# power.net
KiCad netlist of a schematic drawn in Altium Designer
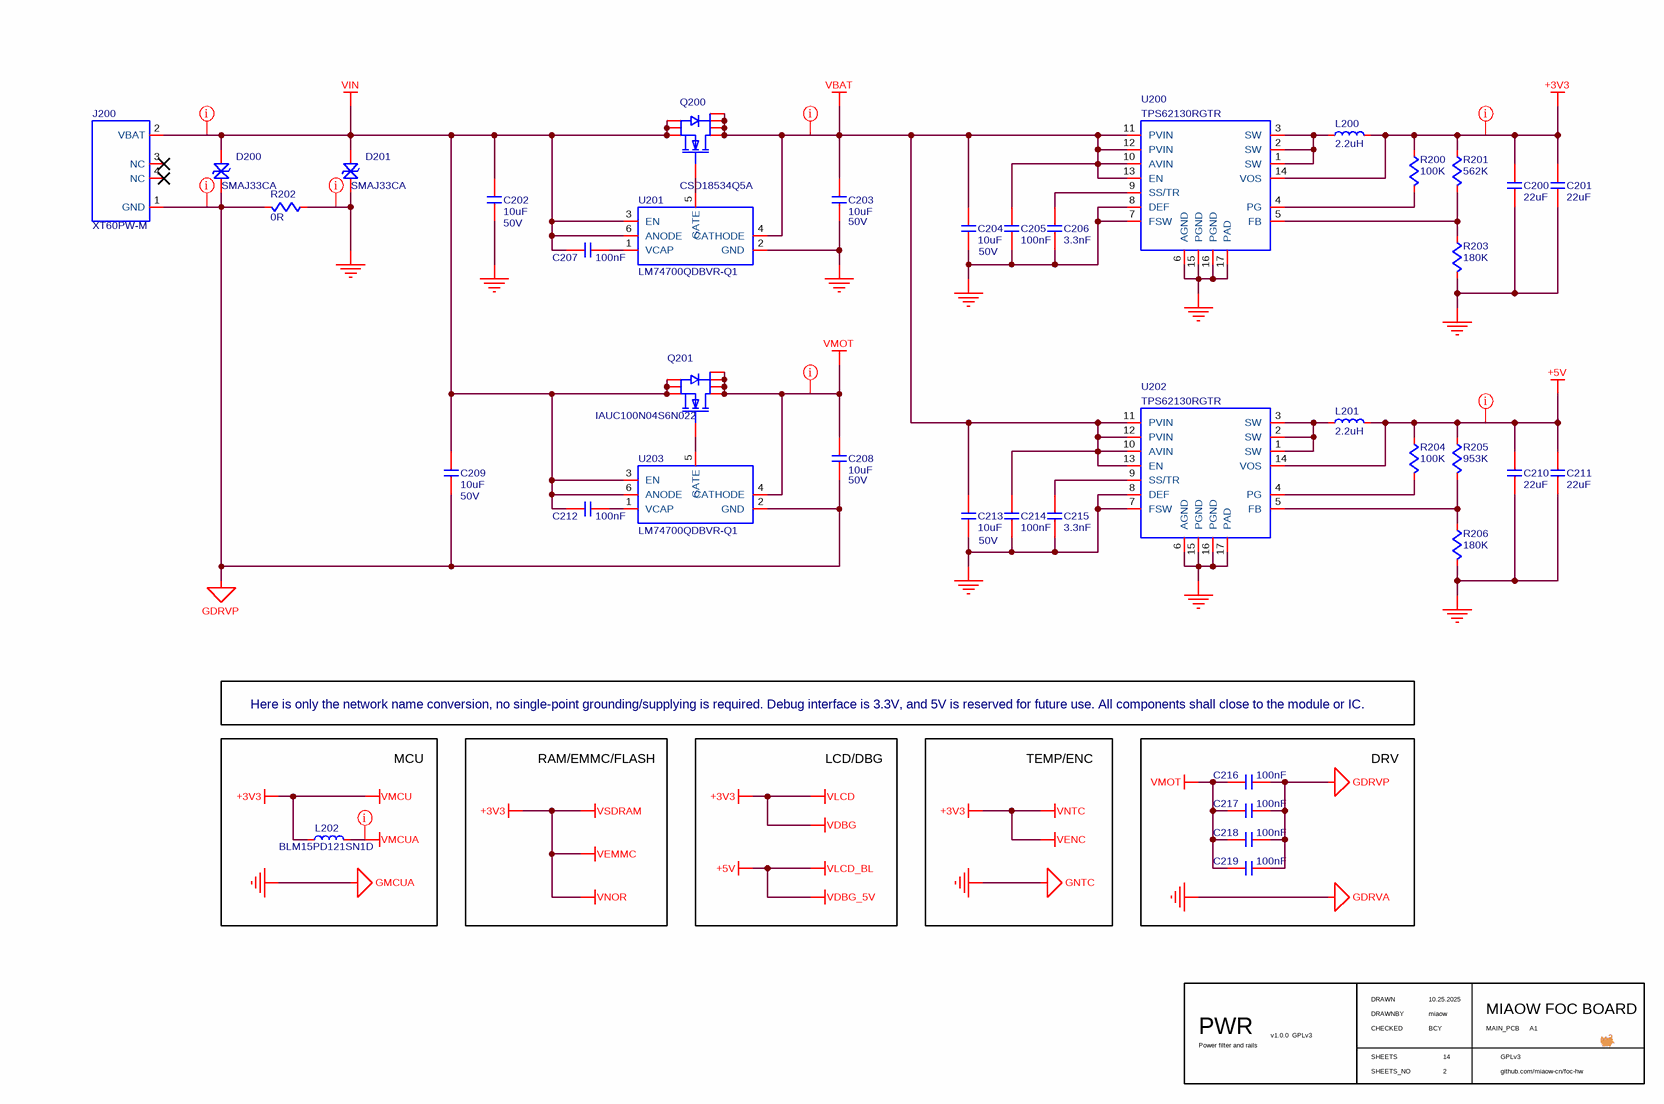
[diagram p0: power.schdoc]

(export (version "E")
  (design (tool "Eeschema 10.0.6"))
  (components
    (comp (ref "C200")
      (value "22uF")
      (footprint "mw:C0805")
      (fields (field (name "VOLTAGE") "25V") (field (name "Comment") "C-NOMO"))
      (libsource (lib "mw") (part "C-NOMO"))
    )
    (comp (ref "C201")
      (value "22uF")
      (footprint "mw:C0805")
      (fields (field (name "VOLTAGE") "25V") (field (name "Comment") "C-NOMO"))
      (libsource (lib "mw") (part "C-NOMO"))
    )
    (comp (ref "C202")
      (value "10uF")
      (footprint "mw:C0805")
      (fields (field (name "VOLTAGE") "50V") (field (name "Comment") "C-NOMO"))
      (libsource (lib "mw") (part "C-NOMO"))
    )
    (comp (ref "C203")
      (value "10uF")
      (footprint "mw:C0805")
      (fields (field (name "VOLTAGE") "50V") (field (name "Comment") "C-NOMO"))
      (libsource (lib "mw") (part "C-NOMO"))
    )
    (comp (ref "C204")
      (value "10uF")
      (footprint "mw:C0805")
      (fields (field (name "VOLTAGE") "50V") (field (name "Comment") "C-NOMO"))
      (libsource (lib "mw") (part "C-NOMO"))
    )
    (comp (ref "C205")
      (value "100nF")
      (footprint "mw:C0603")
      (fields (field (name "VOLTAGE") "25V") (field (name "Comment") "C-NOMO"))
      (libsource (lib "mw") (part "C-NOMO"))
    )
    (comp (ref "C206")
      (value "3.3nF")
      (footprint "mw:C0402")
      (fields (field (name "VOLTAGE") "25V") (field (name "Comment") "C-NOMO"))
      (libsource (lib "mw") (part "C-NOMO"))
    )
    (comp (ref "C207")
      (value "100nF")
      (footprint "mw:C0402")
      (fields (field (name "VOLTAGE") "25V") (field (name "Comment") "C-NOMO"))
      (libsource (lib "mw") (part "C-NOMO"))
    )
    (comp (ref "C208")
      (value "10uF")
      (footprint "mw:C0805")
      (fields (field (name "VOLTAGE") "50V") (field (name "Comment") "C-NOMO"))
      (libsource (lib "mw") (part "C-NOMO"))
    )
    (comp (ref "C209")
      (value "10uF")
      (footprint "mw:C0805")
      (fields (field (name "VOLTAGE") "50V") (field (name "Comment") "C-NOMO"))
      (libsource (lib "mw") (part "C-NOMO"))
    )
    (comp (ref "C210")
      (value "22uF")
      (footprint "mw:C0805")
      (fields (field (name "VOLTAGE") "25V") (field (name "Comment") "C-NOMO"))
      (libsource (lib "mw") (part "C-NOMO"))
    )
    (comp (ref "C211")
      (value "22uF")
      (footprint "mw:C0805")
      (fields (field (name "VOLTAGE") "25V") (field (name "Comment") "C-NOMO"))
      (libsource (lib "mw") (part "C-NOMO"))
    )
    (comp (ref "C212")
      (value "100nF")
      (footprint "mw:C0402")
      (fields (field (name "VOLTAGE") "25V") (field (name "Comment") "C-NOMO"))
      (libsource (lib "mw") (part "C-NOMO"))
    )
    (comp (ref "C213")
      (value "10uF")
      (footprint "mw:C0805")
      (fields (field (name "VOLTAGE") "50V") (field (name "Comment") "C-NOMO"))
      (libsource (lib "mw") (part "C-NOMO"))
    )
    (comp (ref "C214")
      (value "100nF")
      (footprint "mw:C0603")
      (fields (field (name "VOLTAGE") "25V") (field (name "Comment") "C-NOMO"))
      (libsource (lib "mw") (part "C-NOMO"))
    )
    (comp (ref "C215")
      (value "3.3nF")
      (footprint "mw:C0402")
      (fields (field (name "VOLTAGE") "25V") (field (name "Comment") "C-NOMO"))
      (libsource (lib "mw") (part "C-NOMO"))
    )
    (comp (ref "C216")
      (value "100nF")
      (footprint "mw:C0603")
      (fields (field (name "VOLTAGE") "25V") (field (name "Comment") "C-NOMO"))
      (libsource (lib "mw") (part "C-NOMO"))
    )
    (comp (ref "C217")
      (value "100nF")
      (footprint "mw:C0603")
      (fields (field (name "VOLTAGE") "25V") (field (name "Comment") "C-NOMO"))
      (libsource (lib "mw") (part "C-NOMO"))
    )
    (comp (ref "C218")
      (value "100nF")
      (footprint "mw:C0603")
      (fields (field (name "VOLTAGE") "25V") (field (name "Comment") "C-NOMO"))
      (libsource (lib "mw") (part "C-NOMO"))
    )
    (comp (ref "C219")
      (value "100nF")
      (footprint "mw:C0603")
      (fields (field (name "VOLTAGE") "25V") (field (name "Comment") "C-NOMO"))
      (libsource (lib "mw") (part "C-NOMO"))
    )
    (comp (ref "D200")
      (value "SMAJ33CA")
      (footprint "mw:SMAJ33CA")
      (description "TVS/ESD")
      (libsource (lib "mw") (part "SMAJ33CA"))
    )
    (comp (ref "D201")
      (value "SMAJ33CA")
      (footprint "mw:SMAJ33CA")
      (description "TVS/ESD")
      (libsource (lib "mw") (part "SMAJ33CA"))
    )
    (comp (ref "J200")
      (value "XT60PW-M")
      (footprint "mw:XT60PW-M")
      (description "CONNECTOR - dc supply")
      (libsource (lib "mw") (part "XT60PW-M"))
    )
    (comp (ref "L200")
      (value "2.2uH")
      (footprint "mw:FXL0420")
      (fields (field (name "Comment") "L") (field (name "PUBLISHER") "Altium Limited"))
      (libsource (lib "mw") (part "L"))
    )
    (comp (ref "L201")
      (value "2.2uH")
      (footprint "mw:FXL0420")
      (fields (field (name "Comment") "L") (field (name "PUBLISHER") "Altium Limited"))
      (libsource (lib "mw") (part "L"))
    )
    (comp (ref "L202")
      (value "BLM15PD121SN1D")
      (footprint "mw:L0402")
      (fields (field (name "PUBLISHER") "Altium Limited"))
      (libsource (lib "mw") (part "L"))
    )
    (comp (ref "Q200")
      (value "CSD18534Q5A")
      (footprint "mw:CSD18534Q5A")
      (description "NMOS")
      (libsource (lib "mw") (part "CSD18534Q5A"))
    )
    (comp (ref "Q201")
      (value "IAUC100N04S6N022")
      (footprint "mw:IAUC100N04S6N022")
      (description "NMOS")
      (libsource (lib "mw") (part "IAUC100N04S6N022"))
    )
    (comp (ref "R200")
      (value "100K")
      (footprint "mw:R0402")
      (fields (field (name "Comment") "R"))
      (libsource (lib "mw") (part "R"))
    )
    (comp (ref "R201")
      (value "562K")
      (footprint "mw:R0603")
      (fields (field (name "Comment") "R"))
      (libsource (lib "mw") (part "R"))
    )
    (comp (ref "R202")
      (value "0R")
      (footprint "mw:R1206")
      (fields (field (name "Comment") "R"))
      (libsource (lib "mw") (part "R"))
    )
    (comp (ref "R203")
      (value "180K")
      (footprint "mw:R0603")
      (fields (field (name "Comment") "R"))
      (libsource (lib "mw") (part "R"))
    )
    (comp (ref "R204")
      (value "100K")
      (footprint "mw:R0402")
      (fields (field (name "Comment") "R"))
      (libsource (lib "mw") (part "R"))
    )
    (comp (ref "R205")
      (value "953K")
      (footprint "mw:R0603")
      (fields (field (name "Comment") "R"))
      (libsource (lib "mw") (part "R"))
    )
    (comp (ref "R206")
      (value "180K")
      (footprint "mw:R0603")
      (fields (field (name "Comment") "R"))
      (libsource (lib "mw") (part "R"))
    )
    (comp (ref "U200")
      (value "TPS62130RGTR")
      (footprint "mw:TPS62130RGTR")
      (libsource (lib "mw") (part "TPS62130RGTR"))
    )
    (comp (ref "U201")
      (value "LM74700QDBVR-Q1")
      (footprint "mw:LM74700QDBVR-Q1")
      (description "IDEAL DIODE")
      (libsource (lib "mw") (part "LM74700QDBVR-Q1"))
    )
    (comp (ref "U202")
      (value "TPS62130RGTR")
      (footprint "mw:TPS62130RGTR")
      (libsource (lib "mw") (part "TPS62130RGTR"))
    )
    (comp (ref "U203")
      (value "LM74700QDBVR-Q1")
      (footprint "mw:LM74700QDBVR-Q1")
      (description "IDEAL DIODE")
      (libsource (lib "mw") (part "LM74700QDBVR-Q1"))
    )
  )
  (nets
    (net (code "1") (name "+3V3") (class "Default")
      (node (ref "C200") (pin "2") (pinfunction "2_2") (pintype "passive"))
      (node (ref "C201") (pin "2") (pinfunction "2_2") (pintype "passive"))
      (node (ref "L200") (pin "2") (pinfunction "2_2") (pintype "passive"))
      (node (ref "L202") (pin "1") (pinfunction "1_1") (pintype "passive"))
      (node (ref "R200") (pin "2") (pinfunction "2_2") (pintype "passive"))
      (node (ref "R201") (pin "2") (pinfunction "2_2") (pintype "passive"))
      (node (ref "U200") (pin "14") (pinfunction "VOS_14") (pintype "passive"))
    )
    (net (code "2") (name "+5V") (class "Default")
      (node (ref "C210") (pin "2") (pinfunction "2_2") (pintype "passive"))
      (node (ref "C211") (pin "2") (pinfunction "2_2") (pintype "passive"))
      (node (ref "L201") (pin "2") (pinfunction "2_2") (pintype "passive"))
      (node (ref "R204") (pin "2") (pinfunction "2_2") (pintype "passive"))
      (node (ref "R205") (pin "2") (pinfunction "2_2") (pintype "passive"))
      (node (ref "U202") (pin "14") (pinfunction "VOS_14") (pintype "passive"))
    )
    (net (code "3") (name "GDRVA") (class "Default")
      (node (ref "C200") (pin "1") (pinfunction "1_1") (pintype "passive"))
      (node (ref "C201") (pin "1") (pinfunction "1_1") (pintype "passive"))
      (node (ref "C202") (pin "1") (pinfunction "1_1") (pintype "passive"))
      (node (ref "C203") (pin "1") (pinfunction "1_1") (pintype "passive"))
      (node (ref "C204") (pin "1") (pinfunction "1_1") (pintype "passive"))
      (node (ref "C205") (pin "1") (pinfunction "1_1") (pintype "passive"))
      (node (ref "C206") (pin "1") (pinfunction "1_1") (pintype "passive"))
      (node (ref "C210") (pin "1") (pinfunction "1_1") (pintype "passive"))
      (node (ref "C211") (pin "1") (pinfunction "1_1") (pintype "passive"))
      (node (ref "C213") (pin "1") (pinfunction "1_1") (pintype "passive"))
      (node (ref "C214") (pin "1") (pinfunction "1_1") (pintype "passive"))
      (node (ref "C215") (pin "1") (pinfunction "1_1") (pintype "passive"))
      (node (ref "D201") (pin "1") (pinfunction "1_1") (pintype "passive"))
      (node (ref "R202") (pin "2") (pinfunction "2_2") (pintype "passive"))
      (node (ref "R203") (pin "1") (pinfunction "1_1") (pintype "passive"))
      (node (ref "R206") (pin "1") (pinfunction "1_1") (pintype "passive"))
      (node (ref "U200") (pin "15") (pinfunction "PGND_15") (pintype "passive"))
      (node (ref "U200") (pin "16") (pinfunction "PGND_16") (pintype "passive"))
      (node (ref "U200") (pin "17") (pinfunction "PAD_17") (pintype "passive"))
      (node (ref "U200") (pin "6") (pinfunction "AGND_6") (pintype "passive"))
      (node (ref "U200") (pin "7") (pinfunction "FSW_7") (pintype "passive"))
      (node (ref "U200") (pin "8") (pinfunction "DEF_8") (pintype "passive"))
      (node (ref "U201") (pin "2") (pinfunction "GND_2") (pintype "passive"))
      (node (ref "U202") (pin "15") (pinfunction "PGND_15") (pintype "passive"))
      (node (ref "U202") (pin "16") (pinfunction "PGND_16") (pintype "passive"))
      (node (ref "U202") (pin "17") (pinfunction "PAD_17") (pintype "passive"))
      (node (ref "U202") (pin "6") (pinfunction "AGND_6") (pintype "passive"))
      (node (ref "U202") (pin "7") (pinfunction "FSW_7") (pintype "passive"))
      (node (ref "U202") (pin "8") (pinfunction "DEF_8") (pintype "passive"))
    )
    (net (code "4") (name "GDRVP") (class "Default")
      (node (ref "C208") (pin "1") (pinfunction "1_1") (pintype "passive"))
      (node (ref "C209") (pin "1") (pinfunction "1_1") (pintype "passive"))
      (node (ref "C216") (pin "1") (pinfunction "1_1") (pintype "passive"))
      (node (ref "C217") (pin "1") (pinfunction "1_1") (pintype "passive"))
      (node (ref "C218") (pin "1") (pinfunction "1_1") (pintype "passive"))
      (node (ref "C219") (pin "1") (pinfunction "1_1") (pintype "passive"))
      (node (ref "D200") (pin "1") (pinfunction "1_1") (pintype "passive"))
      (node (ref "J200") (pin "1") (pinfunction "GND_1") (pintype "passive"))
      (node (ref "R202") (pin "1") (pinfunction "1_1") (pintype "passive"))
      (node (ref "U203") (pin "2") (pinfunction "GND_2") (pintype "passive"))
    )
    (net (code "5") (name "Net-(L200-Pad1)") (class "Default")
      (node (ref "L200") (pin "1") (pinfunction "1_1") (pintype "passive"))
      (node (ref "U200") (pin "1") (pinfunction "SW_1") (pintype "passive"))
      (node (ref "U200") (pin "2") (pinfunction "SW_2") (pintype "passive"))
      (node (ref "U200") (pin "3") (pinfunction "SW_3") (pintype "passive"))
    )
    (net (code "6") (name "Net-(L201-Pad1)") (class "Default")
      (node (ref "L201") (pin "1") (pinfunction "1_1") (pintype "passive"))
      (node (ref "U202") (pin "1") (pinfunction "SW_1") (pintype "passive"))
      (node (ref "U202") (pin "2") (pinfunction "SW_2") (pintype "passive"))
      (node (ref "U202") (pin "3") (pinfunction "SW_3") (pintype "passive"))
    )
    (net (code "7") (name "Net-(Q200-G)") (class "Default")
      (node (ref "Q200") (pin "4") (pinfunction "G_4") (pintype "passive"))
      (node (ref "U201") (pin "5") (pinfunction "GATE_5") (pintype "passive"))
    )
    (net (code "8") (name "Net-(Q201-G)") (class "Default")
      (node (ref "Q201") (pin "4") (pinfunction "G_4") (pintype "passive"))
      (node (ref "U203") (pin "5") (pinfunction "GATE_5") (pintype "passive"))
    )
    (net (code "9") (name "Net-(U200-FB)") (class "Default")
      (node (ref "R201") (pin "1") (pinfunction "1_1") (pintype "passive"))
      (node (ref "R203") (pin "2") (pinfunction "2_2") (pintype "passive"))
      (node (ref "U200") (pin "5") (pinfunction "FB_5") (pintype "passive"))
    )
    (net (code "10") (name "Net-(U200-PG)") (class "Default")
      (node (ref "R200") (pin "1") (pinfunction "1_1") (pintype "passive"))
      (node (ref "U200") (pin "4") (pinfunction "PG_4") (pintype "passive"))
    )
    (net (code "11") (name "Net-(U200-SS{slash}TR)") (class "Default")
      (node (ref "C206") (pin "2") (pinfunction "2_2") (pintype "passive"))
      (node (ref "U200") (pin "9") (pinfunction "SS/TR_9") (pintype "passive"))
    )
    (net (code "12") (name "Net-(U201-VCAP)") (class "Default")
      (node (ref "C207") (pin "2") (pinfunction "2_2") (pintype "passive"))
      (node (ref "U201") (pin "1") (pinfunction "VCAP_1") (pintype "passive"))
    )
    (net (code "13") (name "Net-(U202-FB)") (class "Default")
      (node (ref "R205") (pin "1") (pinfunction "1_1") (pintype "passive"))
      (node (ref "R206") (pin "2") (pinfunction "2_2") (pintype "passive"))
      (node (ref "U202") (pin "5") (pinfunction "FB_5") (pintype "passive"))
    )
    (net (code "14") (name "Net-(U202-PG)") (class "Default")
      (node (ref "R204") (pin "1") (pinfunction "1_1") (pintype "passive"))
      (node (ref "U202") (pin "4") (pinfunction "PG_4") (pintype "passive"))
    )
    (net (code "15") (name "Net-(U202-SS{slash}TR)") (class "Default")
      (node (ref "C215") (pin "2") (pinfunction "2_2") (pintype "passive"))
      (node (ref "U202") (pin "9") (pinfunction "SS/TR_9") (pintype "passive"))
    )
    (net (code "16") (name "Net-(U203-VCAP)") (class "Default")
      (node (ref "C212") (pin "2") (pinfunction "2_2") (pintype "passive"))
      (node (ref "U203") (pin "1") (pinfunction "VCAP_1") (pintype "passive"))
    )
    (net (code "17") (name "VBAT") (class "Default")
      (node (ref "C203") (pin "2") (pinfunction "2_2") (pintype "passive"))
      (node (ref "C204") (pin "2") (pinfunction "2_2") (pintype "passive"))
      (node (ref "C205") (pin "2") (pinfunction "2_2") (pintype "passive"))
      (node (ref "C213") (pin "2") (pinfunction "2_2") (pintype "passive"))
      (node (ref "C214") (pin "2") (pinfunction "2_2") (pintype "passive"))
      (node (ref "Q200") (pin "5") (pinfunction "D_5") (pintype "passive"))
      (node (ref "Q200") (pin "6") (pinfunction "D_6") (pintype "passive"))
      (node (ref "Q200") (pin "7") (pinfunction "D_7") (pintype "passive"))
      (node (ref "Q200") (pin "8") (pinfunction "D_8") (pintype "passive"))
      (node (ref "U200") (pin "10") (pinfunction "AVIN_10") (pintype "passive"))
      (node (ref "U200") (pin "11") (pinfunction "PVIN_11") (pintype "passive"))
      (node (ref "U200") (pin "12") (pinfunction "PVIN_12") (pintype "passive"))
      (node (ref "U200") (pin "13") (pinfunction "EN_13") (pintype "passive"))
      (node (ref "U201") (pin "4") (pinfunction "CATHODE_4") (pintype "passive"))
      (node (ref "U202") (pin "10") (pinfunction "AVIN_10") (pintype "passive"))
      (node (ref "U202") (pin "11") (pinfunction "PVIN_11") (pintype "passive"))
      (node (ref "U202") (pin "12") (pinfunction "PVIN_12") (pintype "passive"))
      (node (ref "U202") (pin "13") (pinfunction "EN_13") (pintype "passive"))
    )
    (net (code "18") (name "VIN") (class "Default")
      (node (ref "C202") (pin "2") (pinfunction "2_2") (pintype "passive"))
      (node (ref "C207") (pin "1") (pinfunction "1_1") (pintype "passive"))
      (node (ref "C209") (pin "2") (pinfunction "2_2") (pintype "passive"))
      (node (ref "C212") (pin "1") (pinfunction "1_1") (pintype "passive"))
      (node (ref "D200") (pin "2") (pinfunction "2_2") (pintype "passive"))
      (node (ref "D201") (pin "2") (pinfunction "2_2") (pintype "passive"))
      (node (ref "J200") (pin "2") (pinfunction "VBAT_2") (pintype "passive"))
      (node (ref "Q200") (pin "1") (pinfunction "S_1") (pintype "passive"))
      (node (ref "Q200") (pin "2") (pinfunction "S_2") (pintype "passive"))
      (node (ref "Q200") (pin "3") (pinfunction "S_3") (pintype "passive"))
      (node (ref "Q201") (pin "1") (pinfunction "S_1") (pintype "passive"))
      (node (ref "Q201") (pin "2") (pinfunction "S_2") (pintype "passive"))
      (node (ref "Q201") (pin "3") (pinfunction "S_3") (pintype "passive"))
      (node (ref "U201") (pin "3") (pinfunction "EN_3") (pintype "passive"))
      (node (ref "U201") (pin "6") (pinfunction "ANODE_6") (pintype "passive"))
      (node (ref "U203") (pin "3") (pinfunction "EN_3") (pintype "passive"))
      (node (ref "U203") (pin "6") (pinfunction "ANODE_6") (pintype "passive"))
    )
    (net (code "19") (name "VMCUA") (class "Default")
      (node (ref "L202") (pin "2") (pinfunction "2_2") (pintype "passive"))
    )
    (net (code "20") (name "VMOT") (class "Default")
      (node (ref "C208") (pin "2") (pinfunction "2_2") (pintype "passive"))
      (node (ref "C216") (pin "2") (pinfunction "2_2") (pintype "passive"))
      (node (ref "C217") (pin "2") (pinfunction "2_2") (pintype "passive"))
      (node (ref "C218") (pin "2") (pinfunction "2_2") (pintype "passive"))
      (node (ref "C219") (pin "2") (pinfunction "2_2") (pintype "passive"))
      (node (ref "Q201") (pin "5") (pinfunction "D_5") (pintype "passive"))
      (node (ref "Q201") (pin "6") (pinfunction "D_6") (pintype "passive"))
      (node (ref "Q201") (pin "7") (pinfunction "D_7") (pintype "passive"))
      (node (ref "Q201") (pin "8") (pinfunction "D_8") (pintype "passive"))
      (node (ref "U203") (pin "4") (pinfunction "CATHODE_4") (pintype "passive"))
    )
    (net (code "21") (name "unconnected-(J200-NC-Pad3)") (class "Default")
      (node (ref "J200") (pin "3") (pinfunction "NC_3") (pintype "passive+no_connect"))
    )
    (net (code "22") (name "unconnected-(J200-NC-Pad4)") (class "Default")
      (node (ref "J200") (pin "4") (pinfunction "NC_4") (pintype "passive+no_connect"))
    )
  )
)
